# yandex_test.net
KiCad netlist of a schematic drawn in Altium Designer
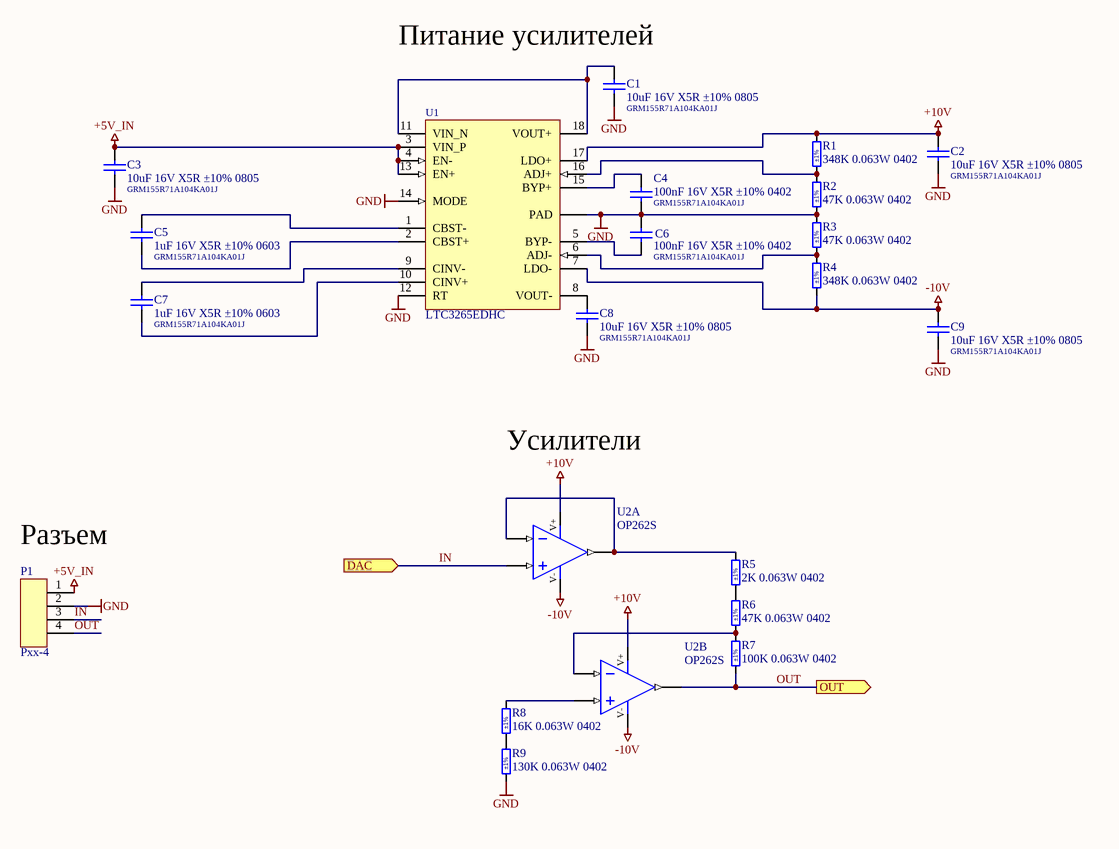
[diagram p0: yandex_test.SchDoc]

(export (version "E")
  (design (tool "Eeschema 10.0.6"))
  (components
    (comp (ref "C1")
      (value "10uF 16V X5R ±10%")
      (footprint "CAP_SMD:0805")
      (description "Ceramic capacitor")
      (fields
        (field (name "VOLTAGE") "16V")
        (field (name "TOLERANCE") "±10%")
        (field (name "NAME") "GRM155R71A104KA01J")
      )
      (libsource (lib "Passive") (part "Capacitor ceramic"))
    )
    (comp (ref "C2")
      (value "10uF 16V X5R ±10%")
      (footprint "CAP_SMD:0805")
      (description "Ceramic capacitor")
      (fields
        (field (name "VOLTAGE") "16V")
        (field (name "TOLERANCE") "±10%")
        (field (name "NAME") "GRM155R71A104KA01J")
      )
      (libsource (lib "Passive") (part "Capacitor ceramic"))
    )
    (comp (ref "C3")
      (value "10uF 16V X5R ±10%")
      (footprint "CAP_SMD:0805")
      (description "Ceramic capacitor")
      (fields
        (field (name "VOLTAGE") "16V")
        (field (name "TOLERANCE") "±10%")
        (field (name "NAME") "GRM155R71A104KA01J")
      )
      (libsource (lib "Passive") (part "Capacitor ceramic"))
    )
    (comp (ref "C4")
      (value "100nF 16V X5R ±10%")
      (footprint "CAP_SMD:0402")
      (description "Ceramic capacitor")
      (fields
        (field (name "VOLTAGE") "16V")
        (field (name "TOLERANCE") "±10%")
        (field (name "NAME") "GRM155R71A104KA01J")
      )
      (libsource (lib "Passive") (part "Capacitor ceramic"))
    )
    (comp (ref "C5")
      (value "1uF 16V X5R ±10%")
      (footprint "CAP_SMD:0603")
      (description "Ceramic capacitor")
      (fields
        (field (name "VOLTAGE") "16V")
        (field (name "TOLERANCE") "±10%")
        (field (name "NAME") "GRM155R71A104KA01J")
      )
      (libsource (lib "Passive") (part "Capacitor ceramic"))
    )
    (comp (ref "C6")
      (value "100nF 16V X5R ±10%")
      (footprint "CAP_SMD:0402")
      (description "Ceramic capacitor")
      (fields
        (field (name "VOLTAGE") "16V")
        (field (name "TOLERANCE") "±10%")
        (field (name "NAME") "GRM155R71A104KA01J")
      )
      (libsource (lib "Passive") (part "Capacitor ceramic"))
    )
    (comp (ref "C7")
      (value "1uF 16V X5R ±10%")
      (footprint "CAP_SMD:0603")
      (description "Ceramic capacitor")
      (fields
        (field (name "VOLTAGE") "16V")
        (field (name "TOLERANCE") "±10%")
        (field (name "NAME") "GRM155R71A104KA01J")
      )
      (libsource (lib "Passive") (part "Capacitor ceramic"))
    )
    (comp (ref "C8")
      (value "10uF 16V X5R ±10%")
      (footprint "CAP_SMD:0805")
      (description "Ceramic capacitor")
      (fields
        (field (name "VOLTAGE") "16V")
        (field (name "TOLERANCE") "±10%")
        (field (name "NAME") "GRM155R71A104KA01J")
      )
      (libsource (lib "Passive") (part "Capacitor ceramic"))
    )
    (comp (ref "C9")
      (value "10uF 16V X5R ±10%")
      (footprint "CAP_SMD:0805")
      (description "Ceramic capacitor")
      (fields
        (field (name "VOLTAGE") "16V")
        (field (name "TOLERANCE") "±10%")
        (field (name "NAME") "GRM155R71A104KA01J")
      )
      (libsource (lib "Passive") (part "Capacitor ceramic"))
    )
    (comp (ref "P1")
      (value "Pxx-4")
      (footprint "CONN_PLx:PBD4_2.54")
      (libsource (lib "CONN_PLx") (part "Pxx-4"))
    )
    (comp (ref "R1")
      (value "348K 0.063W")
      (footprint "RES_SMD:0402")
      (description "Thin Film Chip Resistor")
      (fields (field (name "POWER") "0.063W") (field (name "TOLERANCE") "±1%"))
      (libsource (lib "Passive") (part "Resistor"))
    )
    (comp (ref "R2")
      (value "47K 0.063W")
      (footprint "RES_SMD:0402")
      (description "Thin Film Chip Resistor")
      (fields (field (name "POWER") "0.063W") (field (name "TOLERANCE") "±1%"))
      (libsource (lib "Passive") (part "Resistor"))
    )
    (comp (ref "R3")
      (value "47K 0.063W")
      (footprint "RES_SMD:0402")
      (description "Thin Film Chip Resistor")
      (fields (field (name "POWER") "0.063W") (field (name "TOLERANCE") "±1%"))
      (libsource (lib "Passive") (part "Resistor"))
    )
    (comp (ref "R4")
      (value "348K 0.063W")
      (footprint "RES_SMD:0402")
      (description "Thin Film Chip Resistor")
      (fields (field (name "POWER") "0.063W") (field (name "TOLERANCE") "±1%"))
      (libsource (lib "Passive") (part "Resistor"))
    )
    (comp (ref "R5")
      (value "2K 0.063W")
      (footprint "RES_SMD:0402")
      (description "Thin Film Chip Resistor")
      (fields (field (name "POWER") "0.063W") (field (name "TOLERANCE") "±1%"))
      (libsource (lib "Passive") (part "Resistor"))
    )
    (comp (ref "R6")
      (value "47K 0.063W")
      (footprint "RES_SMD:0402")
      (description "Thin Film Chip Resistor")
      (fields (field (name "POWER") "0.063W") (field (name "TOLERANCE") "±1%"))
      (libsource (lib "Passive") (part "Resistor"))
    )
    (comp (ref "R7")
      (value "100K 0.063W")
      (footprint "RES_SMD:0402")
      (description "Thin Film Chip Resistor")
      (fields (field (name "POWER") "0.063W") (field (name "TOLERANCE") "±1%"))
      (libsource (lib "Passive") (part "Resistor"))
    )
    (comp (ref "R8")
      (value "16K 0.063W")
      (footprint "RES_SMD:0402")
      (description "Thin Film Chip Resistor")
      (fields (field (name "POWER") "0.063W") (field (name "TOLERANCE") "±1%"))
      (libsource (lib "Passive") (part "Resistor"))
    )
    (comp (ref "R9")
      (value "130K 0.063W")
      (footprint "RES_SMD:0402")
      (description "Thin Film Chip Resistor")
      (fields (field (name "POWER") "0.063W") (field (name "TOLERANCE") "±1%"))
      (libsource (lib "Passive") (part "Resistor"))
    )
    (comp (ref "U1")
      (value "LTC3265EDHC")
      (description "Low Noise Dual Supply\r\nwith Boost and Inverting\r\nCharge Pumps")
      (libsource (lib "IC_DCDC") (part "LTC3265"))
    )
    (comp (ref "U2A")
      (value "OP262S")
      (footprint "CSP_BGA:UFLGA6")
      (description "Rail to rail opamp")
      (libsource (lib "IC_OPAMP_COMP") (part "OPAMP"))
    )
    (comp (ref "U2B")
      (value "OP262S")
      (footprint "CSP_BGA:UFLGA6")
      (description "Rail to rail opamp")
      (libsource (lib "IC_OPAMP_COMP") (part "OPAMP"))
    )
  )
  (nets
    (net (code "1") (name "+5V_IN") (class "Default")
      (node (ref "C3") (pin "1") (pinfunction "1_1") (pintype "passive"))
      (node (ref "P1") (pin "1") (pinfunction "1_1") (pintype "passive"))
      (node (ref "U1") (pin "13") (pinfunction "EN+_13") (pintype "input"))
      (node (ref "U1") (pin "3") (pinfunction "VIN_P_3") (pintype "passive"))
      (node (ref "U1") (pin "4") (pinfunction "EN-_4") (pintype "input"))
    )
    (net (code "2") (name "+10V") (class "Default")
      (node (ref "C2") (pin "1") (pinfunction "1_1") (pintype "passive"))
      (node (ref "R1") (pin "2") (pinfunction "2_2") (pintype "passive"))
      (node (ref "U1") (pin "17") (pinfunction "LDO+_17") (pintype "passive"))
      (node (ref "U2A") (pin "6") (pinfunction "V+_6") (pintype "power_in"))
      (node (ref "U2B") (pin "6") (pinfunction "V+_6") (pintype "power_in"))
    )
    (net (code "3") (name "-10V") (class "Default")
      (node (ref "C9") (pin "1") (pinfunction "1_1") (pintype "passive"))
      (node (ref "R4") (pin "1") (pinfunction "1_1") (pintype "passive"))
      (node (ref "U1") (pin "7") (pinfunction "LDO-_7") (pintype "passive"))
      (node (ref "U2A") (pin "2") (pinfunction "V-_2") (pintype "power_in"))
      (node (ref "U2B") (pin "2") (pinfunction "V-_2") (pintype "power_in"))
    )
    (net (code "4") (name "/IN") (class "Default")
      (node (ref "P1") (pin "3") (pinfunction "3_3") (pintype "passive"))
      (node (ref "U2A") (pin "3") (pinfunction "IN+_3") (pintype "input"))
    )
    (net (code "5") (name "/OUT") (class "Default")
      (node (ref "P1") (pin "4") (pinfunction "4_4") (pintype "passive"))
      (node (ref "R7") (pin "1") (pinfunction "1_1") (pintype "passive"))
      (node (ref "U2B") (pin "1") (pinfunction "OUT_1") (pintype "output"))
    )
    (net (code "6") (name "GND") (class "Default")
      (node (ref "C1") (pin "2") (pinfunction "2_2") (pintype "passive"))
      (node (ref "C2") (pin "2") (pinfunction "2_2") (pintype "passive"))
      (node (ref "C3") (pin "2") (pinfunction "2_2") (pintype "passive"))
      (node (ref "C4") (pin "2") (pinfunction "2_2") (pintype "passive"))
      (node (ref "C6") (pin "1") (pinfunction "1_1") (pintype "passive"))
      (node (ref "C8") (pin "2") (pinfunction "2_2") (pintype "passive"))
      (node (ref "C9") (pin "2") (pinfunction "2_2") (pintype "passive"))
      (node (ref "P1") (pin "2") (pinfunction "2_2") (pintype "passive"))
      (node (ref "R2") (pin "1") (pinfunction "1_1") (pintype "passive"))
      (node (ref "R3") (pin "2") (pinfunction "2_2") (pintype "passive"))
      (node (ref "R9") (pin "1") (pinfunction "1_1") (pintype "passive"))
      (node (ref "U1") (pin "12") (pinfunction "RT_12") (pintype "passive"))
      (node (ref "U1") (pin "14") (pinfunction "MODE_14") (pintype "input"))
      (node (ref "U1") (pin "19") (pinfunction "PAD_19") (pintype "passive"))
    )
    (net (code "7") (name "Net-(R5-Pad1)") (class "Default")
      (node (ref "R5") (pin "1") (pinfunction "1_1") (pintype "passive"))
      (node (ref "R6") (pin "2") (pinfunction "2_2") (pintype "passive"))
    )
    (net (code "8") (name "Net-(R8-Pad1)") (class "Default")
      (node (ref "R8") (pin "1") (pinfunction "1_1") (pintype "passive"))
      (node (ref "R9") (pin "2") (pinfunction "2_2") (pintype "passive"))
    )
    (net (code "9") (name "Net-(U1-ADJ+)") (class "Default")
      (node (ref "R1") (pin "1") (pinfunction "1_1") (pintype "passive"))
      (node (ref "R2") (pin "2") (pinfunction "2_2") (pintype "passive"))
      (node (ref "U1") (pin "16") (pinfunction "ADJ+_16") (pintype "input"))
    )
    (net (code "10") (name "Net-(U1-ADJ-)") (class "Default")
      (node (ref "R3") (pin "1") (pinfunction "1_1") (pintype "passive"))
      (node (ref "R4") (pin "2") (pinfunction "2_2") (pintype "passive"))
      (node (ref "U1") (pin "6") (pinfunction "ADJ-_6") (pintype "input"))
    )
    (net (code "11") (name "Net-(U1-BYP+)") (class "Default")
      (node (ref "C4") (pin "1") (pinfunction "1_1") (pintype "passive"))
      (node (ref "U1") (pin "15") (pinfunction "BYP+_15") (pintype "passive"))
    )
    (net (code "12") (name "Net-(U1-BYP-)") (class "Default")
      (node (ref "C6") (pin "2") (pinfunction "2_2") (pintype "passive"))
      (node (ref "U1") (pin "5") (pinfunction "BYP-_5") (pintype "passive"))
    )
    (net (code "13") (name "Net-(U1-CBST+)") (class "Default")
      (node (ref "C5") (pin "2") (pinfunction "2_2") (pintype "passive"))
      (node (ref "U1") (pin "2") (pinfunction "CBST+_2") (pintype "passive"))
    )
    (net (code "14") (name "Net-(U1-CBST-)") (class "Default")
      (node (ref "C5") (pin "1") (pinfunction "1_1") (pintype "passive"))
      (node (ref "U1") (pin "1") (pinfunction "CBST-_1") (pintype "passive"))
    )
    (net (code "15") (name "Net-(U1-CINV+)") (class "Default")
      (node (ref "C7") (pin "2") (pinfunction "2_2") (pintype "passive"))
      (node (ref "U1") (pin "10") (pinfunction "CINV+_10") (pintype "passive"))
    )
    (net (code "16") (name "Net-(U1-CINV-)") (class "Default")
      (node (ref "C7") (pin "1") (pinfunction "1_1") (pintype "passive"))
      (node (ref "U1") (pin "9") (pinfunction "CINV-_9") (pintype "passive"))
    )
    (net (code "17") (name "Net-(U1-VIN_N)") (class "Default")
      (node (ref "C1") (pin "1") (pinfunction "1_1") (pintype "passive"))
      (node (ref "U1") (pin "11") (pinfunction "VIN_N_11") (pintype "passive"))
      (node (ref "U1") (pin "18") (pinfunction "VOUT+_18") (pintype "passive"))
    )
    (net (code "18") (name "Net-(U1-VOUT-)") (class "Default")
      (node (ref "C8") (pin "1") (pinfunction "1_1") (pintype "passive"))
      (node (ref "U1") (pin "8") (pinfunction "VOUT-_8") (pintype "passive"))
    )
    (net (code "19") (name "Net-(U2A-IN-)") (class "Default")
      (node (ref "R5") (pin "2") (pinfunction "2_2") (pintype "passive"))
      (node (ref "U2A") (pin "1") (pinfunction "OUT_1") (pintype "output"))
      (node (ref "U2A") (pin "4") (pinfunction "IN-_4") (pintype "input"))
    )
    (net (code "20") (name "Net-(U2B-IN+)") (class "Default")
      (node (ref "R8") (pin "2") (pinfunction "2_2") (pintype "passive"))
      (node (ref "U2B") (pin "3") (pinfunction "IN+_3") (pintype "input"))
    )
    (net (code "21") (name "Net-(U2B-IN-)") (class "Default")
      (node (ref "R6") (pin "1") (pinfunction "1_1") (pintype "passive"))
      (node (ref "R7") (pin "2") (pinfunction "2_2") (pintype "passive"))
      (node (ref "U2B") (pin "4") (pinfunction "IN-_4") (pintype "input"))
    )
  )
)
